# MACH_LUC.net
KiCad netlist of a schematic drawn in Altium Designer
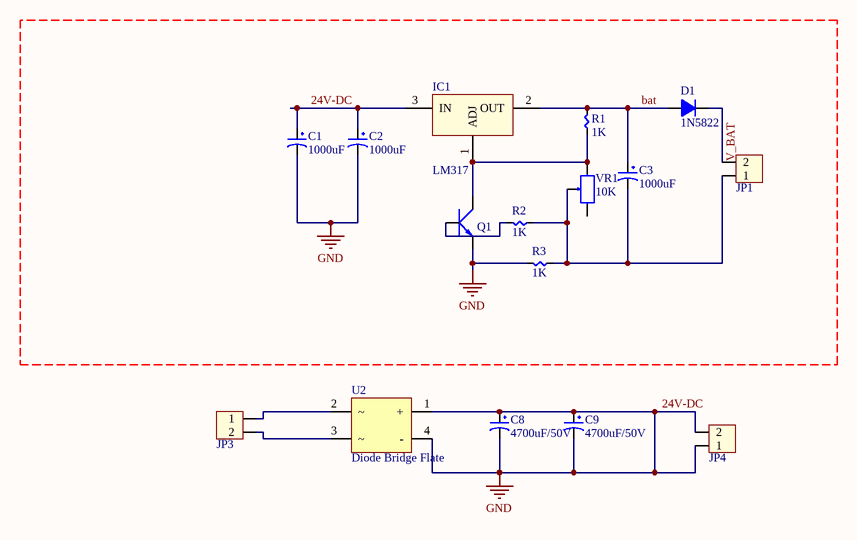
[diagram p0: MACH_LUC.SchDoc]

(export (version "E")
  (design (tool "Eeschema 10.0.6"))
  (components
    (comp (ref "C1")
      (value "1000uF")
      (footprint "CP2/4")
      (description "C 47uF/50V , 220uF/16V")
      (libsource (lib "Luyen_Schematics") (part "CP2"))
    )
    (comp (ref "C2")
      (value "1000uF")
      (footprint "CP2/4")
      (description "C 47uF/50V , 220uF/16V")
      (libsource (lib "Luyen_Schematics") (part "CP2"))
    )
    (comp (ref "C3")
      (value "1000uF")
      (footprint "CP2/4")
      (description "C 47uF/50V , 220uF/16V")
      (libsource (lib "Luyen_Schematics") (part "CP2"))
    )
    (comp (ref "C8")
      (value "4700uF/50V")
      (footprint "CP4/8.5")
      (description "Cap 4700uF/50V")
      (libsource (lib "Luyen_Schematics") (part "CP7"))
    )
    (comp (ref "C9")
      (value "4700uF/50V")
      (footprint "CP4/8.5")
      (description "Cap 4700uF/50V")
      (libsource (lib "Luyen_Schematics") (part "CP7"))
    )
    (comp (ref "D1")
      (value "1N5822")
      (footprint "D5A")
      (description "Diode 5A")
      (libsource (lib "Luyen_Schematics") (part "D5A"))
    )
    (comp (ref "IC1")
      (value "LM317")
      (footprint "PART:QTO-220")
      (description "Adj Voltage +1.2 -> +37V")
      (libsource (lib "Luyen_Schematics") (part "LM317"))
    )
    (comp (ref "JP1") (value "Connector 2") (footprint "CON2") (libsource (lib "") (part "CON2_1")))
    (comp (ref "JP3")
      (value "Connector 2")
      (footprint "CON2")
      (libsource (lib "Luyen_Schematics") (part "CON2"))
    )
    (comp (ref "JP4") (value "Connector 2") (footprint "CON2") (libsource (lib "") (part "CON2_1")))
    (comp (ref "Q1")
      (value "C9014")
      (footprint "PART:QTO-92")
      (description "P 600mW, EBC")
      (libsource (lib "Luyen_Schematics") (part "NPN_EBC"))
    )
    (comp (ref "R1")
      (value "1K")
      (footprint "SM-0805")
      (description "Resistor")
      (libsource (lib "THU VIEN CHAN") (part "RES 0805 BUT"))
    )
    (comp (ref "R2")
      (value "1K")
      (footprint "SM-0805")
      (description "Resistor")
      (libsource (lib "THU VIEN CHAN") (part "RES 0805 BUT"))
    )
    (comp (ref "R3")
      (value "1K")
      (footprint "SM-0805")
      (description "Resistor")
      (libsource (lib "THU VIEN CHAN") (part "RES 0805 BUT"))
    )
    (comp (ref "U2")
      (value "Diode Bridge Flate")
      (footprint "DIODE BRIDGE(FLAT)")
      (description "Diode Bridge")
      (libsource (lib "Luyen_Schematics") (part "Diode Bridge Flate"))
    )
    (comp (ref "VR1")
      (value "10K")
      (footprint "PART:VR")
      (description "Var Resistor")
      (libsource (lib "Luyen_Schematics") (part "VR"))
    )
  )
  (nets
    (net (code "1") (name "/V_BAT") (class "Default")
      (node (ref "D1") (pin "2") (pinfunction "K_2") (pintype "passive"))
      (node (ref "JP1") (pin "2") (pinfunction "2_2") (pintype "passive"))
    )
    (net (code "2") (name "/bat") (class "Default")
      (node (ref "C3") (pin "1") (pinfunction "1_1") (pintype "passive"))
      (node (ref "D1") (pin "1") (pinfunction "A_1") (pintype "passive"))
      (node (ref "IC1") (pin "2") (pinfunction "OUT_2") (pintype "passive"))
      (node (ref "R1") (pin "1") (pinfunction "1_1") (pintype "passive"))
    )
    (net (code "3") (name "GND") (class "Default")
      (node (ref "C1") (pin "1") (pinfunction "1_1") (pintype "passive"))
      (node (ref "C1") (pin "2") (pinfunction "2_2") (pintype "passive"))
      (node (ref "C2") (pin "1") (pinfunction "1_1") (pintype "passive"))
      (node (ref "C2") (pin "2") (pinfunction "2_2") (pintype "passive"))
      (node (ref "C8") (pin "1") (pinfunction "1_1") (pintype "passive"))
      (node (ref "C8") (pin "2") (pinfunction "2_2") (pintype "passive"))
      (node (ref "C9") (pin "1") (pinfunction "1_1") (pintype "passive"))
      (node (ref "C9") (pin "2") (pinfunction "2_2") (pintype "passive"))
      (node (ref "IC1") (pin "3") (pinfunction "IN_3") (pintype "passive"))
      (node (ref "JP4") (pin "1") (pinfunction "1_1") (pintype "passive"))
      (node (ref "JP4") (pin "2") (pinfunction "2_2") (pintype "passive"))
      (node (ref "Q1") (pin "1") (pinfunction "E_1") (pintype "passive"))
      (node (ref "R3") (pin "1") (pinfunction "1_1") (pintype "passive"))
      (node (ref "U2") (pin "1") (pinfunction "+_1") (pintype "passive"))
      (node (ref "U2") (pin "4") (pinfunction "-_4") (pintype "passive"))
    )
    (net (code "4") (name "Net-(C3-Pad2)") (class "Default")
      (node (ref "C3") (pin "2") (pinfunction "2_2") (pintype "passive"))
      (node (ref "JP1") (pin "1") (pinfunction "1_1") (pintype "passive"))
      (node (ref "R2") (pin "2") (pinfunction "2_2") (pintype "passive"))
      (node (ref "R3") (pin "2") (pinfunction "2_2") (pintype "passive"))
      (node (ref "VR1") (pin "2") (pinfunction "2_2") (pintype "passive"))
    )
    (net (code "5") (name "Net-(IC1-ADJ)") (class "Default")
      (node (ref "IC1") (pin "1") (pinfunction "ADJ_1") (pintype "passive"))
      (node (ref "Q1") (pin "3") (pinfunction "C_3") (pintype "passive"))
      (node (ref "R1") (pin "2") (pinfunction "2_2") (pintype "passive"))
      (node (ref "VR1") (pin "3") (pinfunction "3_3") (pintype "passive"))
    )
    (net (code "6") (name "Net-(JP3-Pad1)") (class "Default")
      (node (ref "JP3") (pin "1") (pinfunction "1_1") (pintype "passive"))
      (node (ref "U2") (pin "2") (pinfunction "~_2") (pintype "passive"))
    )
    (net (code "7") (name "Net-(JP3-Pad2)") (class "Default")
      (node (ref "JP3") (pin "2") (pinfunction "2_2") (pintype "passive"))
      (node (ref "U2") (pin "3") (pinfunction "~_3") (pintype "passive"))
    )
    (net (code "8") (name "Net-(Q1-B)") (class "Default")
      (node (ref "Q1") (pin "2") (pinfunction "B_2") (pintype "passive"))
      (node (ref "R2") (pin "1") (pinfunction "1_1") (pintype "passive"))
    )
    (net (code "9") (name "unconnected-(VR1-Pad1)") (class "Default")
      (node (ref "VR1") (pin "1") (pinfunction "1_1") (pintype "passive"))
    )
  )
)
